# OpticDiodes_LEDs.net
KiCad netlist of a schematic drawn in Altium Designer
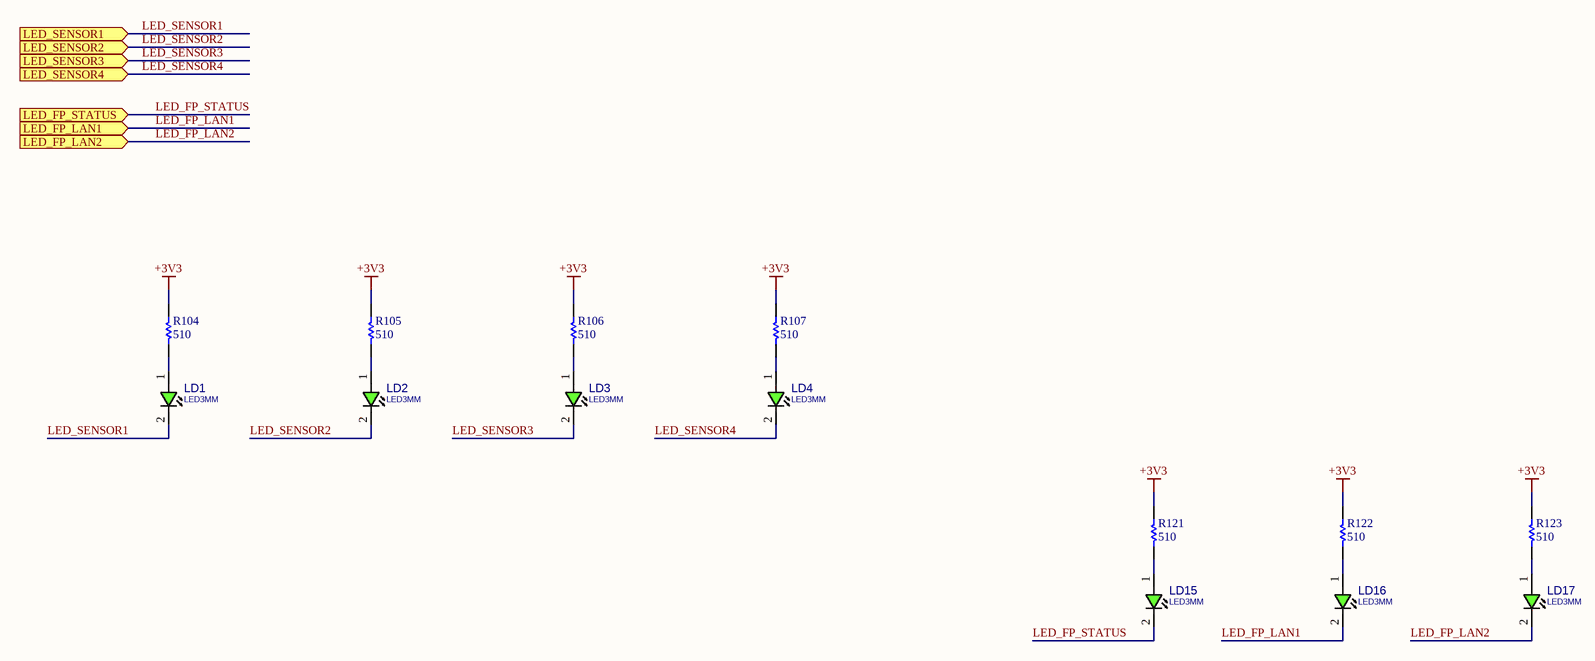
[diagram p0: OpticDiodes+LEDs.SchDoc]

(export (version "E")
  (design (tool "Eeschema 10.0.6"))
  (components
    (comp (ref "LD1")
      (value "LED3MM")
      (footprint "LED3MM")
      (description "LED, THD, 3MM, GREEN")
      (fields (field (name "MANF") "MANF") (field (name "MANF_P#") "MANF_PART#"))
      (libsource (lib "led(diode)") (part "LED_THD_3MM"))
    )
    (comp (ref "LD2")
      (value "LED3MM")
      (footprint "LED3MM")
      (description "LED, THD, 3MM, GREEN")
      (fields (field (name "MANF") "MANF") (field (name "MANF_P#") "MANF_PART#"))
      (libsource (lib "led(diode)") (part "LED_THD_3MM"))
    )
    (comp (ref "LD3")
      (value "LED3MM")
      (footprint "LED3MM")
      (description "LED, THD, 3MM, GREEN")
      (fields (field (name "MANF") "MANF") (field (name "MANF_P#") "MANF_PART#"))
      (libsource (lib "led(diode)") (part "LED_THD_3MM"))
    )
    (comp (ref "LD4")
      (value "LED3MM")
      (footprint "LED3MM")
      (description "LED, THD, 3MM, GREEN")
      (fields (field (name "MANF") "MANF") (field (name "MANF_P#") "MANF_PART#"))
      (libsource (lib "led(diode)") (part "LED_THD_3MM"))
    )
    (comp (ref "LD15")
      (value "LED3MM")
      (footprint "LED3MM")
      (description "LED, THD, 3MM, GREEN")
      (fields (field (name "MANF") "MANF") (field (name "MANF_P#") "MANF_PART#"))
      (libsource (lib "led(diode)") (part "LED_THD_3MM"))
    )
    (comp (ref "LD16")
      (value "LED3MM")
      (footprint "LED3MM")
      (description "LED, THD, 3MM, GREEN")
      (fields (field (name "MANF") "MANF") (field (name "MANF_P#") "MANF_PART#"))
      (libsource (lib "led(diode)") (part "LED_THD_3MM"))
    )
    (comp (ref "LD17")
      (value "LED3MM")
      (footprint "LED3MM")
      (description "LED, THD, 3MM, GREEN")
      (fields (field (name "MANF") "MANF") (field (name "MANF_P#") "MANF_PART#"))
      (libsource (lib "led(diode)") (part "LED_THD_3MM"))
    )
    (comp (ref "R104")
      (value "510")
      (footprint "R0603E")
      (description "Resistor: thick film; SMD")
      (fields
        (field (name "PART NUMBER") "510")
        (field (name "MANUFACTURER") "Vishay or Panasonic")
        (field (name "MANUFACTURER PART NUMBER") "NULL")
      )
      (libsource (lib "Miscellaneous Devices") (part "Res1"))
    )
    (comp (ref "R105")
      (value "510")
      (footprint "R0603E")
      (description "Resistor: thick film; SMD")
      (fields
        (field (name "PART NUMBER") "510")
        (field (name "MANUFACTURER") "Vishay or Panasonic")
        (field (name "MANUFACTURER PART NUMBER") "NULL")
      )
      (libsource (lib "Miscellaneous Devices") (part "Res1"))
    )
    (comp (ref "R106")
      (value "510")
      (footprint "R0603E")
      (description "Resistor: thick film; SMD")
      (fields
        (field (name "PART NUMBER") "510")
        (field (name "MANUFACTURER") "Vishay or Panasonic")
        (field (name "MANUFACTURER PART NUMBER") "NULL")
      )
      (libsource (lib "Miscellaneous Devices") (part "Res1"))
    )
    (comp (ref "R107")
      (value "510")
      (footprint "R0603E")
      (description "Resistor: thick film; SMD")
      (fields
        (field (name "PART NUMBER") "510")
        (field (name "MANUFACTURER") "Vishay or Panasonic")
        (field (name "MANUFACTURER PART NUMBER") "NULL")
      )
      (libsource (lib "Miscellaneous Devices") (part "Res1"))
    )
    (comp (ref "R121")
      (value "510")
      (footprint "R0603E")
      (description "Resistor: thick film; SMD")
      (fields
        (field (name "PART NUMBER") "510")
        (field (name "MANUFACTURER") "Vishay or Panasonic")
        (field (name "MANUFACTURER PART NUMBER") "NULL")
      )
      (libsource (lib "Miscellaneous Devices") (part "Res1"))
    )
    (comp (ref "R122")
      (value "510")
      (footprint "R0603E")
      (description "Resistor: thick film; SMD")
      (fields
        (field (name "PART NUMBER") "510")
        (field (name "MANUFACTURER") "Vishay or Panasonic")
        (field (name "MANUFACTURER PART NUMBER") "NULL")
      )
      (libsource (lib "Miscellaneous Devices") (part "Res1"))
    )
    (comp (ref "R123")
      (value "510")
      (footprint "R0603E")
      (description "Resistor: thick film; SMD")
      (fields
        (field (name "PART NUMBER") "510")
        (field (name "MANUFACTURER") "Vishay or Panasonic")
        (field (name "MANUFACTURER PART NUMBER") "NULL")
      )
      (libsource (lib "Miscellaneous Devices") (part "Res1"))
    )
  )
  (nets
    (net (code "1") (name "+3V3") (class "Default")
      (node (ref "R104") (pin "1") (pinfunction "1_1") (pintype "passive"))
      (node (ref "R105") (pin "1") (pinfunction "1_1") (pintype "passive"))
      (node (ref "R106") (pin "1") (pinfunction "1_1") (pintype "passive"))
      (node (ref "R107") (pin "1") (pinfunction "1_1") (pintype "passive"))
      (node (ref "R121") (pin "1") (pinfunction "1_1") (pintype "passive"))
      (node (ref "R122") (pin "1") (pinfunction "1_1") (pintype "passive"))
      (node (ref "R123") (pin "1") (pinfunction "1_1") (pintype "passive"))
    )
    (net (code "2") (name "/LED_FP_LAN1") (class "Default")
      (node (ref "LD16") (pin "2") (pinfunction "CATHODE_2") (pintype "passive"))
    )
    (net (code "3") (name "/LED_FP_LAN2") (class "Default")
      (node (ref "LD17") (pin "2") (pinfunction "CATHODE_2") (pintype "passive"))
    )
    (net (code "4") (name "/LED_FP_STATUS") (class "Default")
      (node (ref "LD15") (pin "2") (pinfunction "CATHODE_2") (pintype "passive"))
    )
    (net (code "5") (name "/LED_SENSOR1") (class "Default")
      (node (ref "LD1") (pin "2") (pinfunction "CATHODE_2") (pintype "passive"))
    )
    (net (code "6") (name "/LED_SENSOR2") (class "Default")
      (node (ref "LD2") (pin "2") (pinfunction "CATHODE_2") (pintype "passive"))
    )
    (net (code "7") (name "/LED_SENSOR3") (class "Default")
      (node (ref "LD3") (pin "2") (pinfunction "CATHODE_2") (pintype "passive"))
    )
    (net (code "8") (name "/LED_SENSOR4") (class "Default")
      (node (ref "LD4") (pin "2") (pinfunction "CATHODE_2") (pintype "passive"))
    )
    (net (code "9") (name "Net-(LD1-ANODE)") (class "Default")
      (node (ref "LD1") (pin "1") (pinfunction "ANODE_1") (pintype "passive"))
      (node (ref "R104") (pin "2") (pinfunction "2_2") (pintype "passive"))
    )
    (net (code "10") (name "Net-(LD2-ANODE)") (class "Default")
      (node (ref "LD2") (pin "1") (pinfunction "ANODE_1") (pintype "passive"))
      (node (ref "R105") (pin "2") (pinfunction "2_2") (pintype "passive"))
    )
    (net (code "11") (name "Net-(LD3-ANODE)") (class "Default")
      (node (ref "LD3") (pin "1") (pinfunction "ANODE_1") (pintype "passive"))
      (node (ref "R106") (pin "2") (pinfunction "2_2") (pintype "passive"))
    )
    (net (code "12") (name "Net-(LD4-ANODE)") (class "Default")
      (node (ref "LD4") (pin "1") (pinfunction "ANODE_1") (pintype "passive"))
      (node (ref "R107") (pin "2") (pinfunction "2_2") (pintype "passive"))
    )
    (net (code "13") (name "Net-(LD15-ANODE)") (class "Default")
      (node (ref "LD15") (pin "1") (pinfunction "ANODE_1") (pintype "passive"))
      (node (ref "R121") (pin "2") (pinfunction "2_2") (pintype "passive"))
    )
    (net (code "14") (name "Net-(LD16-ANODE)") (class "Default")
      (node (ref "LD16") (pin "1") (pinfunction "ANODE_1") (pintype "passive"))
      (node (ref "R122") (pin "2") (pinfunction "2_2") (pintype "passive"))
    )
    (net (code "15") (name "Net-(LD17-ANODE)") (class "Default")
      (node (ref "LD17") (pin "1") (pinfunction "ANODE_1") (pintype "passive"))
      (node (ref "R123") (pin "2") (pinfunction "2_2") (pintype "passive"))
    )
  )
)
